# Schematic.net
KiCad netlist of a schematic drawn in EasyEDA
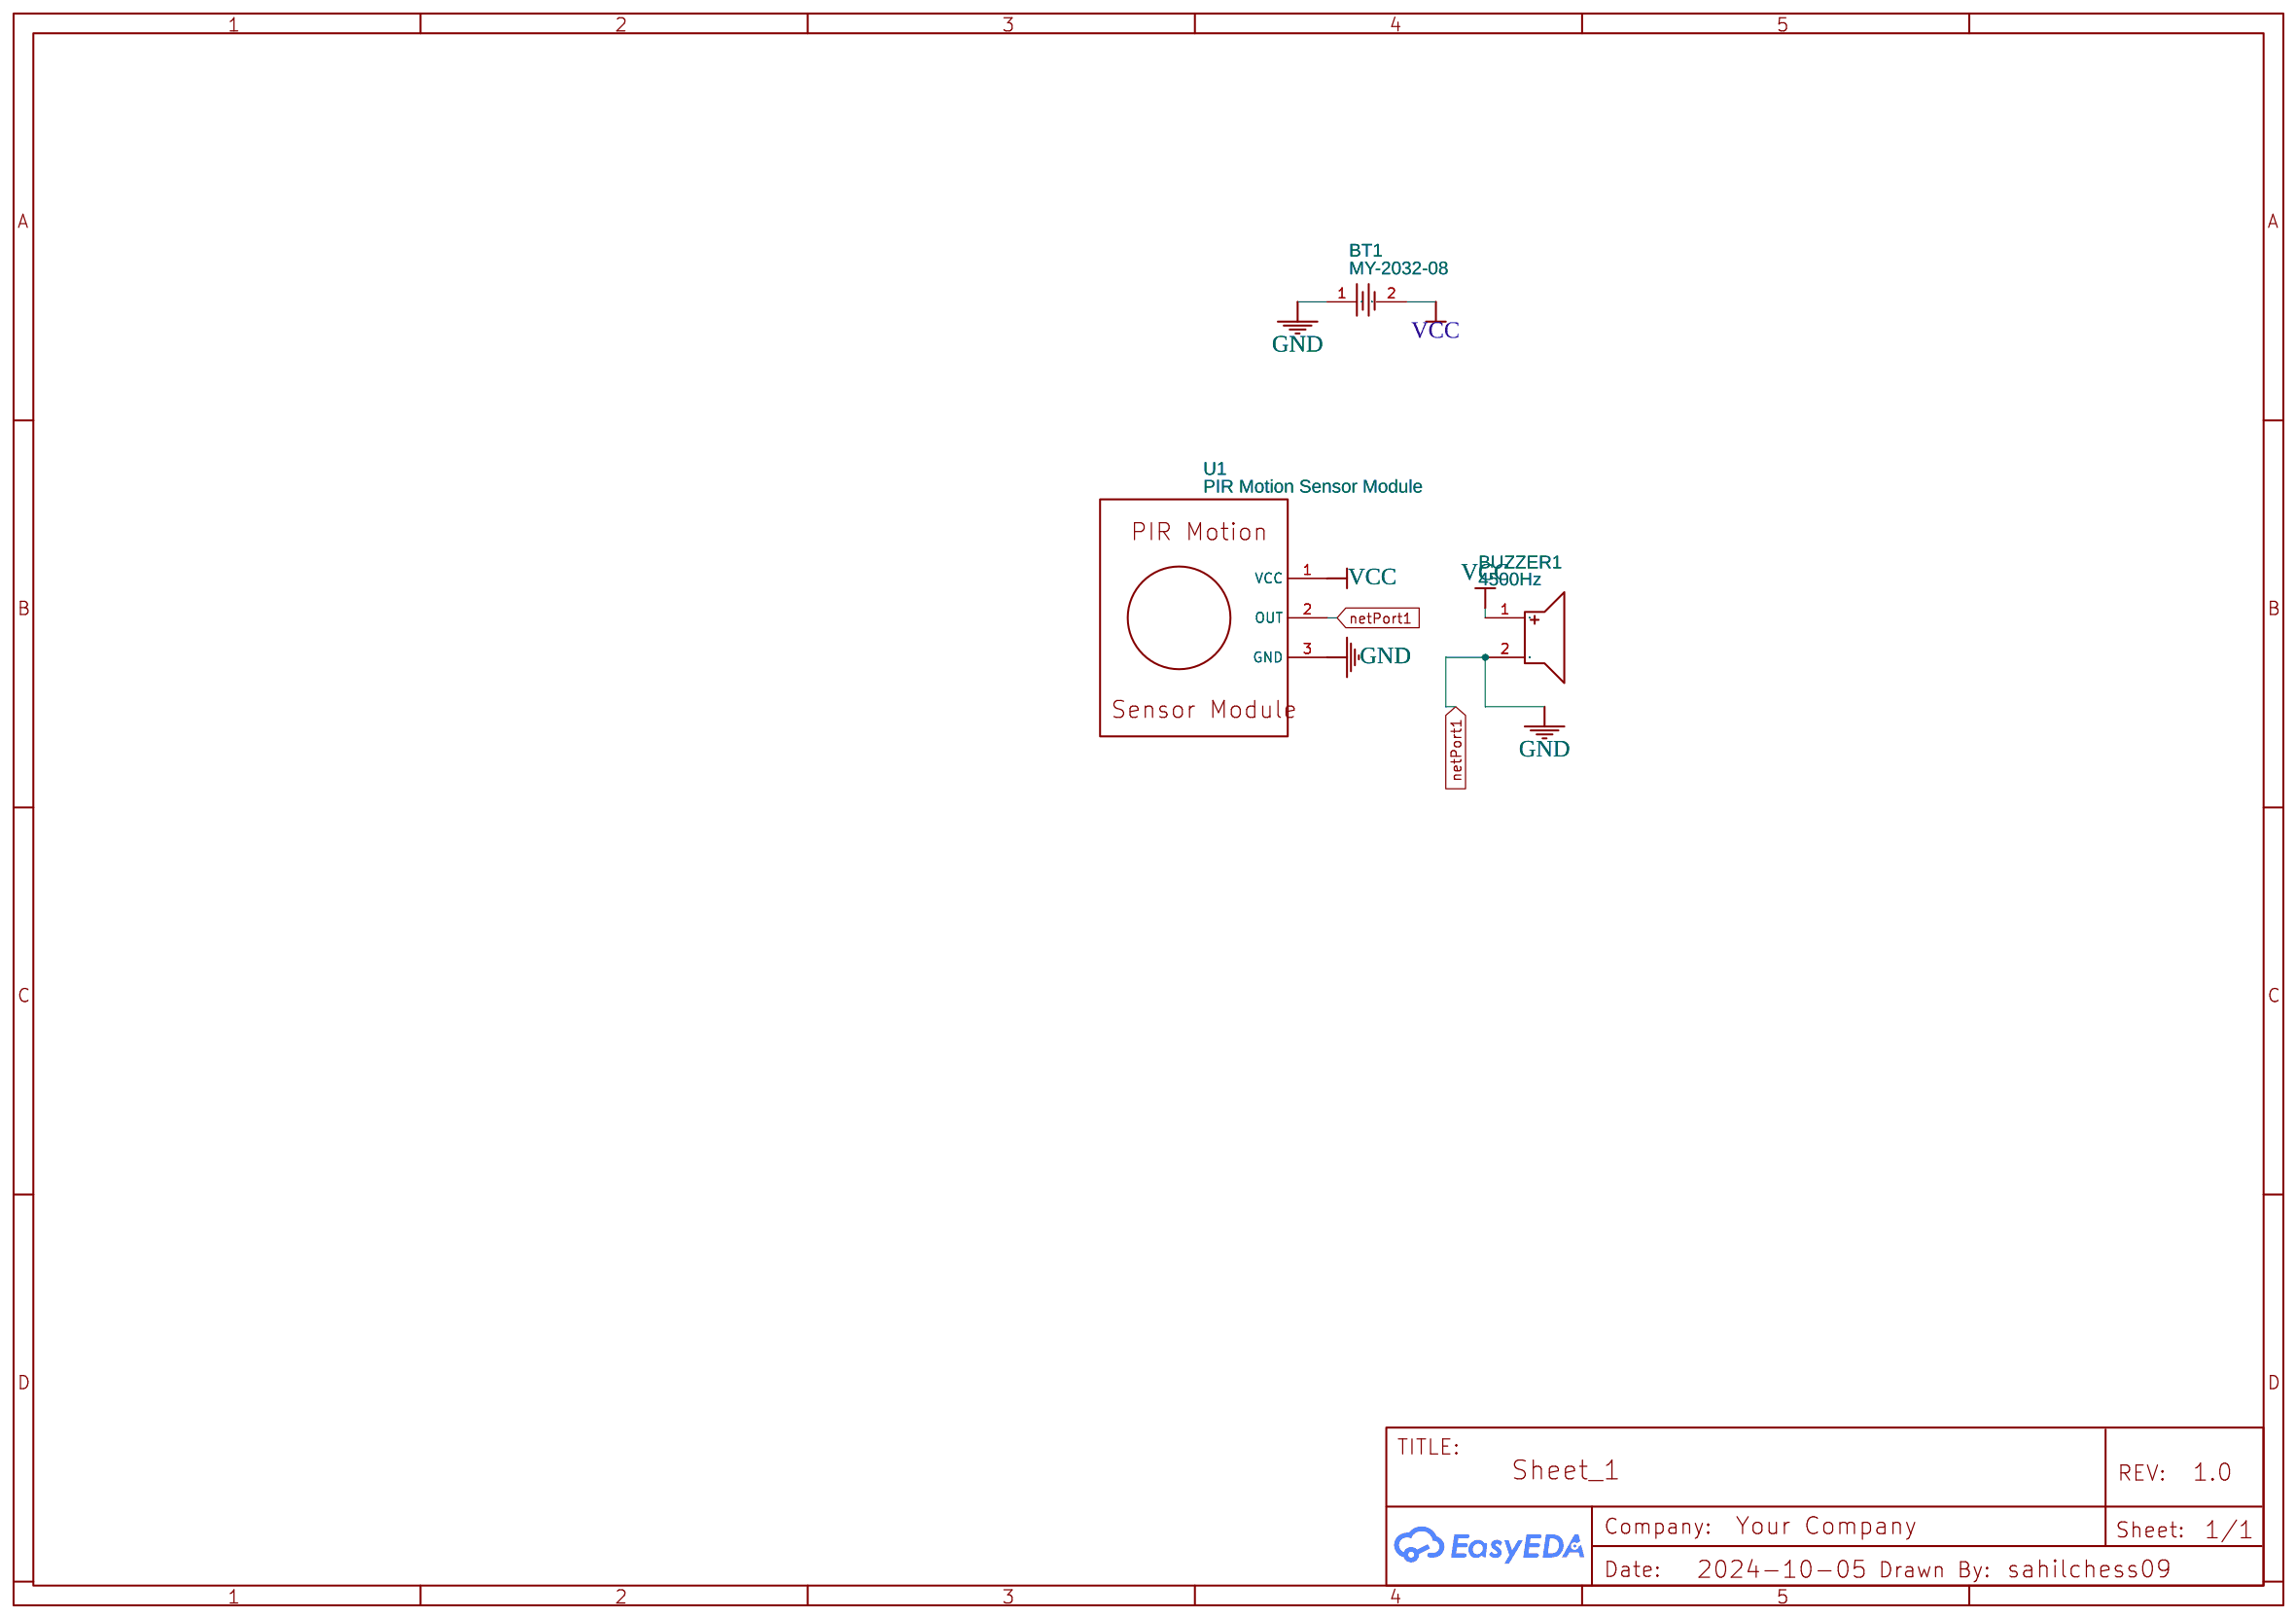
[diagram p0: schematic sheet]

(export (version "E")
  (design (tool "Eeschema 10.0.6"))
  (components
    (comp (ref "BT1")
      (value "MY-2032-08")
      (fields (field (name "Manufacturer") "MYOUNG(美阳)"))
      (libsource (lib "") (part "MY-2032-08"))
    )
    (comp (ref "BUZZER1")
      (value "4500Hz")
      (fields (field (name "Manufacturer Part") "HND-1407B") (field (name "Manufacturer") "华能"))
      (libsource (lib "") (part "HND-1407B"))
    )
    (comp (ref "U1")
      (value "PIR Motion Sensor Module")
      (libsource (lib "") (part "PIR Motion Sensor Module"))
    )
  )
  (nets
    (net (code "1") (name "VCC") (class "Default")
      (node (ref "BT1") (pin "2") (pinfunction "2_2") (pintype "input"))
      (node (ref "BUZZER1") (pin "1") (pinfunction "1_1") (pintype "unspecified"))
      (node (ref "U1") (pin "1") (pinfunction "VCC_1") (pintype "unspecified"))
    )
    (net (code "2") (name "netPort1") (class "Default")
      (node (ref "BT1") (pin "1") (pinfunction "1_1") (pintype "input"))
      (node (ref "BUZZER1") (pin "2") (pinfunction "2_2") (pintype "unspecified"))
      (node (ref "U1") (pin "2") (pinfunction "OUT_2") (pintype "unspecified"))
      (node (ref "U1") (pin "3") (pinfunction "GND_3") (pintype "unspecified"))
    )
  )
)
